# Sch_Power.net
KiCad netlist of a schematic drawn in Altium Designer
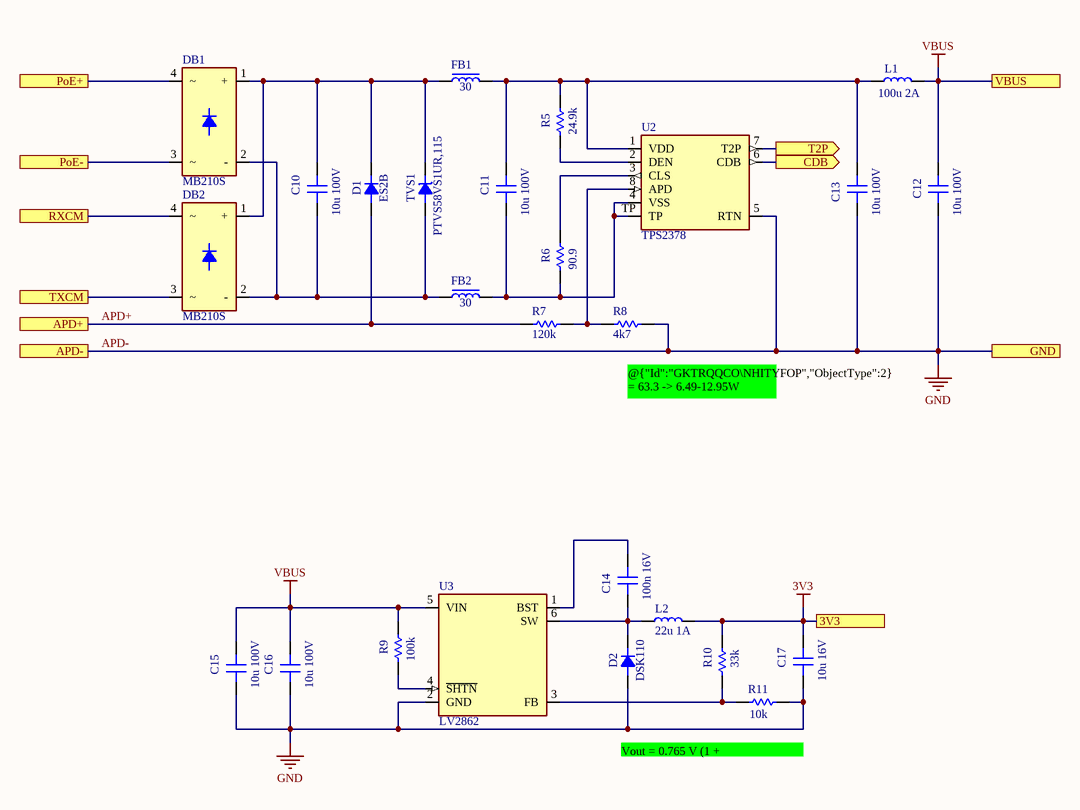
[diagram p0: Sch_Power.SchDoc]

(export (version "E")
  (design (tool "Eeschema 10.0.6"))
  (components
    (comp (ref "C10")
      (value "10u 100V")
      (footprint "CAP_SMD_1210")
      (description "Capacitor SMD - Generic")
      (libsource (lib "AltiumLibrary") (part "CAP_SMD"))
    )
    (comp (ref "C11")
      (value "10u 100V")
      (footprint "CAP_SMD_1210")
      (description "Capacitor SMD - Generic")
      (libsource (lib "AltiumLibrary") (part "CAP_SMD"))
    )
    (comp (ref "C12")
      (value "10u 100V")
      (footprint "CAP_SMD_1210")
      (description "Capacitor SMD - Generic")
      (libsource (lib "AltiumLibrary") (part "CAP_SMD"))
    )
    (comp (ref "C13")
      (value "10u 100V")
      (footprint "CAP_SMD_1210")
      (description "Capacitor SMD - Generic")
      (libsource (lib "AltiumLibrary") (part "CAP_SMD"))
    )
    (comp (ref "C14")
      (value "100n 16V")
      (footprint "CAP_SMD_0603")
      (description "Capacitor SMD - Generic")
      (libsource (lib "AltiumLibrary") (part "CAP_SMD"))
    )
    (comp (ref "C15")
      (value "10u 100V")
      (footprint "CAP_SMD_1210")
      (description "Capacitor SMD - Generic")
      (libsource (lib "AltiumLibrary") (part "CAP_SMD"))
    )
    (comp (ref "C16")
      (value "10u 100V")
      (footprint "CAP_SMD_1210")
      (description "Capacitor SMD - Generic")
      (libsource (lib "AltiumLibrary") (part "CAP_SMD"))
    )
    (comp (ref "C17")
      (value "10u 16V")
      (footprint "CAP_SMD_1210")
      (description "Capacitor SMD - Generic")
      (libsource (lib "AltiumLibrary") (part "CAP_SMD"))
    )
    (comp (ref "D1")
      (value "ES2B")
      (footprint "D_SMA")
      (description "100V 2A Super Fast Recovery Rectifier")
      (libsource (lib "AltiumLibrary") (part "ES1J"))
    )
    (comp (ref "D2")
      (value "DSK110")
      (footprint "D_SMD_SOD123W")
      (description "100V 1A Schottky Barrier Diode")
      (libsource (lib "AltiumLibrary") (part "DIODE_SMD"))
    )
    (comp (ref "DB1")
      (value "MB210S")
      (footprint "IC_MBS")
      (description "100 2A diode bridge")
      (fields (field (name "MF") "Fortune Semiconductor") (field (name "MP") "DW01A"))
      (libsource (lib "AltiumLibrary") (part "MB2S"))
    )
    (comp (ref "DB2")
      (value "MB210S")
      (footprint "IC_MBS")
      (description "100 2A diode bridge")
      (fields (field (name "MF") "Fortune Semiconductor") (field (name "MP") "DW01A"))
      (libsource (lib "AltiumLibrary") (part "MB2S"))
    )
    (comp (ref "FB1")
      (value "30")
      (footprint "FB_SMD_0805")
      (description "Ferrite bead SMD - Generic")
      (libsource (lib "AltiumLibrary") (part "FB_SMD"))
    )
    (comp (ref "FB2")
      (value "30")
      (footprint "FB_SMD_0805")
      (description "Ferrite bead SMD - Generic")
      (libsource (lib "AltiumLibrary") (part "FB_SMD"))
    )
    (comp (ref "L1")
      (value "100u 2A")
      (footprint "IND_SMD7.1x6.6x5")
      (description "Inductor SMD - Generic")
      (libsource (lib "AltiumLibrary") (part "IND_SMD"))
    )
    (comp (ref "L2")
      (value "22u 1A")
      (footprint "IND_SMD3x3x1.2mm")
      (description "Inductor SMD - Generic")
      (libsource (lib "AltiumLibrary") (part "IND_SMD"))
    )
    (comp (ref "R5")
      (value "24.9k")
      (footprint "RES_SMD_0603")
      (description "Resistor SMD - Generic")
      (libsource (lib "AltiumLibrary") (part "RES_SMD"))
    )
    (comp (ref "R6")
      (value "90.9")
      (footprint "RES_SMD_0603")
      (description "Resistor SMD - Generic")
      (libsource (lib "AltiumLibrary") (part "RES_SMD"))
    )
    (comp (ref "R7")
      (value "120k")
      (footprint "RES_SMD_0603")
      (description "Resistor SMD - Generic")
      (libsource (lib "") (part "RES_SMD_1"))
    )
    (comp (ref "R8")
      (value "4k7")
      (footprint "RES_SMD_0603")
      (description "Resistor SMD - Generic")
      (libsource (lib "") (part "RES_SMD_1"))
    )
    (comp (ref "R9")
      (value "100k")
      (footprint "RES_SMD_0603")
      (description "Resistor SMD - Generic")
      (libsource (lib "AltiumLibrary") (part "RES_SMD"))
    )
    (comp (ref "R10")
      (value "33k")
      (footprint "RES_SMD_0603")
      (description "Resistor SMD - Generic")
      (libsource (lib "AltiumLibrary") (part "RES_SMD"))
    )
    (comp (ref "R11")
      (value "10k")
      (footprint "RES_SMD_0603")
      (description "Resistor SMD - Generic")
      (libsource (lib "") (part "RES_SMD_1"))
    )
    (comp (ref "TVS1")
      (value "PTVS58VS1UR,115")
      (footprint "D_SOD123W")
      (description "SMD zener diode - Generic")
      (libsource (lib "AltiumLibrary") (part "ZENER_SMD"))
    )
    (comp (ref "U2")
      (value "TPS2378")
      (footprint "IC_SOIC8_TP")
      (description "IEEE 802.3at PoE High-Power PD Interface")
      (fields (field (name "MF") "Fortune Semiconductor") (field (name "MP") "DW01A"))
      (libsource (lib "AltiumLibrary") (part "TPS2378"))
    )
    (comp (ref "U3")
      (value "LV2862")
      (footprint "IC_SOT23_6")
      (description "Buck converter controller")
      (libsource (lib "AltiumLibrary") (part "LV2862"))
    )
  )
  (nets
    (net (code "1") (name "/APD+") (class "Default")
      (node (ref "D1") (pin "A") (pinfunction "A_A") (pintype "passive"))
      (node (ref "R7") (pin "1") (pinfunction "1_1") (pintype "passive"))
    )
    (net (code "2") (name "/CDB") (class "Default")
      (node (ref "U2") (pin "6") (pinfunction "CDB_6") (pintype "output"))
    )
    (net (code "3") (name "/PoE+") (class "Default")
      (node (ref "DB1") (pin "4") (pinfunction "~_4") (pintype "power_in"))
    )
    (net (code "4") (name "/PoE-") (class "Default")
      (node (ref "DB1") (pin "3") (pinfunction "~_3") (pintype "power_in"))
    )
    (net (code "5") (name "/RXCM") (class "Default")
      (node (ref "DB2") (pin "4") (pinfunction "~_4") (pintype "power_in"))
    )
    (net (code "6") (name "/T2P") (class "Default")
      (node (ref "U2") (pin "7") (pinfunction "T2P_7") (pintype "output"))
    )
    (net (code "7") (name "/TXCM") (class "Default")
      (node (ref "DB2") (pin "3") (pinfunction "~_3") (pintype "power_in"))
    )
    (net (code "8") (name "3V3") (class "Default")
      (node (ref "C17") (pin "1") (pinfunction "1_1") (pintype "passive"))
      (node (ref "L2") (pin "2") (pinfunction "2_2") (pintype "passive"))
      (node (ref "R10") (pin "1") (pinfunction "1_1") (pintype "passive"))
    )
    (net (code "9") (name "GND") (class "Default")
      (node (ref "C12") (pin "2") (pinfunction "2_2") (pintype "passive"))
      (node (ref "C13") (pin "2") (pinfunction "2_2") (pintype "passive"))
      (node (ref "C15") (pin "2") (pinfunction "2_2") (pintype "passive"))
      (node (ref "C16") (pin "2") (pinfunction "2_2") (pintype "passive"))
      (node (ref "C17") (pin "2") (pinfunction "2_2") (pintype "passive"))
      (node (ref "D2") (pin "A") (pinfunction "A_A") (pintype "passive"))
      (node (ref "R11") (pin "2") (pinfunction "2_2") (pintype "passive"))
      (node (ref "R8") (pin "2") (pinfunction "2_2") (pintype "passive"))
      (node (ref "U2") (pin "5") (pinfunction "RTN_5") (pintype "passive"))
      (node (ref "U3") (pin "2") (pinfunction "GND_2") (pintype "power_in"))
    )
    (net (code "10") (name "Net-(DB1-+)") (class "Default")
      (node (ref "C10") (pin "1") (pinfunction "1_1") (pintype "passive"))
      (node (ref "D1") (pin "K") (pinfunction "K_K") (pintype "passive"))
      (node (ref "DB1") (pin "1") (pinfunction "+_1") (pintype "power_in"))
      (node (ref "DB2") (pin "1") (pinfunction "+_1") (pintype "power_in"))
      (node (ref "FB1") (pin "1") (pinfunction "1_1") (pintype "passive"))
      (node (ref "TVS1") (pin "K") (pinfunction "K_K") (pintype "passive"))
    )
    (net (code "11") (name "Net-(DB1--)") (class "Default")
      (node (ref "C10") (pin "2") (pinfunction "2_2") (pintype "passive"))
      (node (ref "DB1") (pin "2") (pinfunction "-_2") (pintype "power_in"))
      (node (ref "DB2") (pin "2") (pinfunction "-_2") (pintype "power_in"))
      (node (ref "FB2") (pin "1") (pinfunction "1_1") (pintype "passive"))
      (node (ref "TVS1") (pin "A") (pinfunction "A_A") (pintype "passive"))
    )
    (net (code "12") (name "Net-(U2-APD)") (class "Default")
      (node (ref "R7") (pin "2") (pinfunction "2_2") (pintype "passive"))
      (node (ref "R8") (pin "1") (pinfunction "1_1") (pintype "passive"))
      (node (ref "U2") (pin "8") (pinfunction "APD_8") (pintype "input"))
    )
    (net (code "13") (name "Net-(U2-CLS)") (class "Default")
      (node (ref "R6") (pin "1") (pinfunction "1_1") (pintype "passive"))
      (node (ref "U2") (pin "3") (pinfunction "CLS_3") (pintype "output"))
    )
    (net (code "14") (name "Net-(U2-DEN)") (class "Default")
      (node (ref "R5") (pin "2") (pinfunction "2_2") (pintype "passive"))
      (node (ref "U2") (pin "2") (pinfunction "DEN_2") (pintype "bidirectional"))
    )
    (net (code "15") (name "Net-(U2-VDD)") (class "Default")
      (node (ref "C11") (pin "1") (pinfunction "1_1") (pintype "passive"))
      (node (ref "C13") (pin "1") (pinfunction "1_1") (pintype "passive"))
      (node (ref "FB1") (pin "2") (pinfunction "2_2") (pintype "passive"))
      (node (ref "L1") (pin "1") (pinfunction "1_1") (pintype "passive"))
      (node (ref "R5") (pin "1") (pinfunction "1_1") (pintype "passive"))
      (node (ref "U2") (pin "1") (pinfunction "VDD_1") (pintype "power_in"))
    )
    (net (code "16") (name "Net-(U2-VSS)") (class "Default")
      (node (ref "C11") (pin "2") (pinfunction "2_2") (pintype "passive"))
      (node (ref "FB2") (pin "2") (pinfunction "2_2") (pintype "passive"))
      (node (ref "R6") (pin "2") (pinfunction "2_2") (pintype "passive"))
      (node (ref "U2") (pin "4") (pinfunction "VSS_4") (pintype "power_in"))
      (node (ref "U2") (pin "TP") (pinfunction "TP_TP") (pintype "power_in"))
    )
    (net (code "17") (name "Net-(U3-BST)") (class "Default")
      (node (ref "C14") (pin "1") (pinfunction "1_1") (pintype "passive"))
      (node (ref "U3") (pin "1") (pinfunction "BST_1") (pintype "power_in"))
    )
    (net (code "18") (name "Net-(U3-FB)") (class "Default")
      (node (ref "R10") (pin "2") (pinfunction "2_2") (pintype "passive"))
      (node (ref "R11") (pin "1") (pinfunction "1_1") (pintype "passive"))
      (node (ref "U3") (pin "3") (pinfunction "FB_3") (pintype "passive"))
    )
    (net (code "19") (name "Net-(U3-SW)") (class "Default")
      (node (ref "C14") (pin "2") (pinfunction "2_2") (pintype "passive"))
      (node (ref "D2") (pin "K") (pinfunction "K_K") (pintype "passive"))
      (node (ref "L2") (pin "1") (pinfunction "1_1") (pintype "passive"))
      (node (ref "U3") (pin "6") (pinfunction "SW_6") (pintype "passive"))
    )
    (net (code "20") (name "Net-(U3-~{SHTN})") (class "Default")
      (node (ref "R9") (pin "2") (pinfunction "2_2") (pintype "passive"))
      (node (ref "U3") (pin "4") (pinfunction "~{SHTN}_4") (pintype "input"))
    )
    (net (code "21") (name "VBUS") (class "Default")
      (node (ref "C12") (pin "1") (pinfunction "1_1") (pintype "passive"))
      (node (ref "C15") (pin "1") (pinfunction "1_1") (pintype "passive"))
      (node (ref "C16") (pin "1") (pinfunction "1_1") (pintype "passive"))
      (node (ref "L1") (pin "2") (pinfunction "2_2") (pintype "passive"))
      (node (ref "R9") (pin "1") (pinfunction "1_1") (pintype "passive"))
      (node (ref "U3") (pin "5") (pinfunction "VIN_5") (pintype "power_in"))
    )
  )
)
